# led_driver.net
KiCad netlist of a schematic drawn in EAGLE
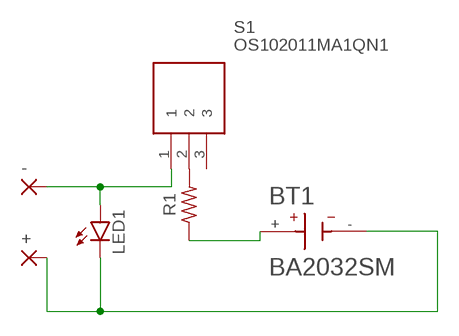
[diagram p0: schematic, sheet 1]

(export (version "E")
  (design (tool "Eeschema 10.0.6"))
  (components
    (comp (ref "+")
      (value "2,54/1,1")
      (footprint "eagle-import:2,54_1,1")
      (libsource (lib "eagle-import") (part "2,54/1,1"))
    )
    (comp (ref "-")
      (value "2,54/1,1")
      (footprint "eagle-import:2,54_1,1")
      (libsource (lib "eagle-import") (part "2,54/1,1"))
    )
    (comp (ref "BT1")
      (value "BA2032SM")
      (footprint "eagle-import:BAT_BA2032SM")
      (fields (field (name "DIGI-KEY_PART_NUMBER") "BA2032SM-ND") (field (name "MF") "MPD"))
      (libsource (lib "eagle-import") (part "BA2032SM"))
    )
    (comp (ref "LED1")
      (value "LED5MM")
      (footprint "eagle-import:LED5MM")
      (libsource (lib "eagle-import") (part "LED5MM"))
    )
    (comp (ref "R1")
      (value "R-US_AXIAL-11.7MM-PITCH")
      (footprint "eagle-import:RESAD1176W63L850D250B")
      (libsource (lib "eagle-import") (part "R-USAXIAL-11.7MM-PITCH_"))
    )
    (comp (ref "S1")
      (value "OS102011MA1QN1")
      (footprint "eagle-import:OS102011MA1QN1")
      (fields (field (name "MOUSER_PART_NUMBER") "611-OS102011MA1QN1"))
      (libsource (lib "eagle-import") (part "OS102011MA1QN1"))
    )
  )
  (nets
    (net (code "1") (name "Net-(+-P)") (class "Default")
      (node (ref "+") (pin "1") (pinfunction "P_1") (pintype "passive"))
      (node (ref "BT1") (pin "-") (pinfunction "-_-") (pintype "passive"))
      (node (ref "LED1") (pin "K") (pinfunction "C_K") (pintype "passive"))
    )
    (net (code "2") (name "Net-(--P)") (class "Default")
      (node (ref "-") (pin "1") (pinfunction "P_1") (pintype "passive"))
      (node (ref "LED1") (pin "A") (pinfunction "A_A") (pintype "passive"))
      (node (ref "S1") (pin "1") (pinfunction "1_1") (pintype "bidirectional"))
    )
    (net (code "3") (name "Net-(BT1-Pad+)") (class "Default")
      (node (ref "BT1") (pin "+") (pinfunction "+_+") (pintype "passive"))
      (node (ref "R1") (pin "1") (pinfunction "1_1") (pintype "passive"))
    )
    (net (code "4") (name "Net-(R1-Pad2)") (class "Default")
      (node (ref "R1") (pin "2") (pinfunction "2_2") (pintype "passive"))
      (node (ref "S1") (pin "2") (pinfunction "2_2") (pintype "bidirectional"))
    )
    (net (code "5") (name "unconnected-(S1-Pad3)") (class "Default")
      (node (ref "S1") (pin "3") (pinfunction "3_3") (pintype "bidirectional"))
    )
  )
)
